# NFC_Demo_Board.net
KiCad netlist of a schematic drawn in EAGLE
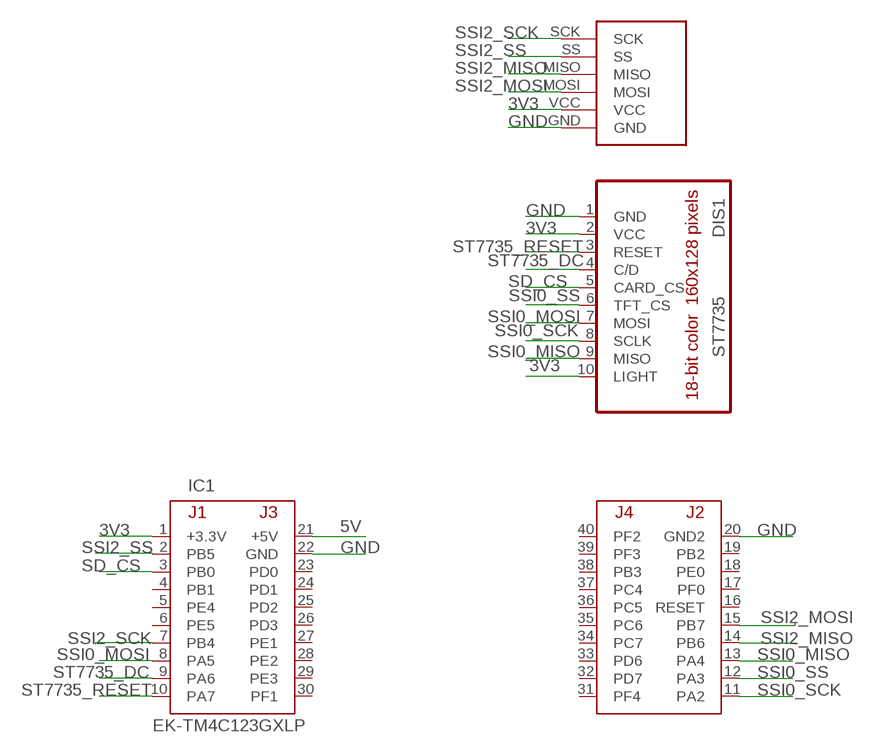
[diagram p0: schematic, sheet 1]

(export (version "E")
  (design (tool "Eeschema 10.0.6"))
  (components
    (comp (ref "DIS1")
      (value "ST7735")
      (footprint "eagle-import:ST7735")
      (libsource (lib "eagle-import") (part "ST7735"))
    )
    (comp (ref "IC1")
      (value "EK-TM4C123GXLP")
      (footprint "eagle-import:TM4C123LAUNCHPAD")
      (libsource (lib "eagle-import") (part "EK-TM4C123GXLP"))
    )
    (comp (ref "U$1")
      (value "ELECHOUSE_PN532_SPI")
      (footprint "eagle-import:ELECHOUSE_PN532_SPI")
      (libsource (lib "eagle-import") (part "ELECHOUSE_PN532_SPI"))
    )
  )
  (nets
    (net (code "1") (name "/3V3") (class "Default")
      (node (ref "DIS1") (pin "10") (pinfunction "LIGHT_10") (pintype "passive"))
      (node (ref "DIS1") (pin "2") (pinfunction "VCC_2") (pintype "power_in"))
      (node (ref "IC1") (pin "1") (pinfunction "+3.3V_1") (pintype "power_in"))
      (node (ref "U$1") (pin "VCC") (pinfunction "VCC_VCC") (pintype "bidirectional"))
    )
    (net (code "2") (name "/5V") (class "Default")
      (node (ref "IC1") (pin "21") (pinfunction "+5V_21") (pintype "power_in"))
    )
    (net (code "3") (name "/GND") (class "Default")
      (node (ref "DIS1") (pin "1") (pinfunction "GND_1") (pintype "power_in"))
      (node (ref "IC1") (pin "20") (pinfunction "GND2_20") (pintype "power_in"))
      (node (ref "IC1") (pin "22") (pinfunction "GND_22") (pintype "power_in"))
      (node (ref "U$1") (pin "GND") (pinfunction "GND_GND") (pintype "bidirectional"))
    )
    (net (code "4") (name "/SD_CS") (class "Default")
      (node (ref "DIS1") (pin "5") (pinfunction "CARD_CS_5") (pintype "input"))
      (node (ref "IC1") (pin "3") (pinfunction "PB0_3") (pintype "bidirectional"))
    )
    (net (code "5") (name "/SSI0_MISO") (class "Default")
      (node (ref "DIS1") (pin "9") (pinfunction "MISO_9") (pintype "output"))
      (node (ref "IC1") (pin "13") (pinfunction "PA4_13") (pintype "bidirectional"))
    )
    (net (code "6") (name "/SSI0_MOSI") (class "Default")
      (node (ref "DIS1") (pin "7") (pinfunction "MOSI_7") (pintype "input"))
      (node (ref "IC1") (pin "8") (pinfunction "PA5_8") (pintype "bidirectional"))
    )
    (net (code "7") (name "/SSI0_SCK") (class "Default")
      (node (ref "DIS1") (pin "8") (pinfunction "SCLK_8") (pintype "input"))
      (node (ref "IC1") (pin "11") (pinfunction "PA2_11") (pintype "bidirectional"))
    )
    (net (code "8") (name "/SSI0_SS") (class "Default")
      (node (ref "DIS1") (pin "6") (pinfunction "TFT_CS_6") (pintype "input"))
      (node (ref "IC1") (pin "12") (pinfunction "PA3_12") (pintype "bidirectional"))
    )
    (net (code "9") (name "/SSI2_MISO") (class "Default")
      (node (ref "IC1") (pin "14") (pinfunction "PB6_14") (pintype "bidirectional"))
      (node (ref "U$1") (pin "MISO") (pinfunction "MISO_MISO") (pintype "bidirectional"))
    )
    (net (code "10") (name "/SSI2_MOSI") (class "Default")
      (node (ref "IC1") (pin "15") (pinfunction "PB7_15") (pintype "bidirectional"))
      (node (ref "U$1") (pin "MOSI") (pinfunction "MOSI_MOSI") (pintype "bidirectional"))
    )
    (net (code "11") (name "/SSI2_SCK") (class "Default")
      (node (ref "IC1") (pin "7") (pinfunction "PB4_7") (pintype "bidirectional"))
      (node (ref "U$1") (pin "SCK") (pinfunction "SCK_SCK") (pintype "bidirectional"))
    )
    (net (code "12") (name "/SSI2_SS") (class "Default")
      (node (ref "IC1") (pin "2") (pinfunction "PB5_2") (pintype "bidirectional"))
      (node (ref "U$1") (pin "SS") (pinfunction "SS_SS") (pintype "bidirectional"))
    )
    (net (code "13") (name "/ST7735_DC") (class "Default")
      (node (ref "DIS1") (pin "4") (pinfunction "C/D_4") (pintype "input"))
      (node (ref "IC1") (pin "9") (pinfunction "PA6_9") (pintype "bidirectional"))
    )
    (net (code "14") (name "/ST7735_RESET") (class "Default")
      (node (ref "DIS1") (pin "3") (pinfunction "RESET_3") (pintype "input"))
      (node (ref "IC1") (pin "10") (pinfunction "PA7_10") (pintype "bidirectional"))
    )
    (net (code "15") (name "unconnected-(IC1-PB1-Pad4)") (class "Default")
      (node (ref "IC1") (pin "4") (pinfunction "PB1_4") (pintype "bidirectional"))
    )
    (net (code "16") (name "unconnected-(IC1-PB2-Pad19)") (class "Default")
      (node (ref "IC1") (pin "19") (pinfunction "PB2_19") (pintype "bidirectional"))
    )
    (net (code "17") (name "unconnected-(IC1-PB3-Pad38)") (class "Default")
      (node (ref "IC1") (pin "38") (pinfunction "PB3_38") (pintype "bidirectional"))
    )
    (net (code "18") (name "unconnected-(IC1-PC4-Pad37)") (class "Default")
      (node (ref "IC1") (pin "37") (pinfunction "PC4_37") (pintype "bidirectional"))
    )
    (net (code "19") (name "unconnected-(IC1-PC5-Pad36)") (class "Default")
      (node (ref "IC1") (pin "36") (pinfunction "PC5_36") (pintype "bidirectional"))
    )
    (net (code "20") (name "unconnected-(IC1-PC6-Pad35)") (class "Default")
      (node (ref "IC1") (pin "35") (pinfunction "PC6_35") (pintype "bidirectional"))
    )
    (net (code "21") (name "unconnected-(IC1-PC7-Pad34)") (class "Default")
      (node (ref "IC1") (pin "34") (pinfunction "PC7_34") (pintype "bidirectional"))
    )
    (net (code "22") (name "unconnected-(IC1-PD0-Pad23)") (class "Default")
      (node (ref "IC1") (pin "23") (pinfunction "PD0_23") (pintype "bidirectional"))
    )
    (net (code "23") (name "unconnected-(IC1-PD1-Pad24)") (class "Default")
      (node (ref "IC1") (pin "24") (pinfunction "PD1_24") (pintype "bidirectional"))
    )
    (net (code "24") (name "unconnected-(IC1-PD2-Pad25)") (class "Default")
      (node (ref "IC1") (pin "25") (pinfunction "PD2_25") (pintype "bidirectional"))
    )
    (net (code "25") (name "unconnected-(IC1-PD3-Pad26)") (class "Default")
      (node (ref "IC1") (pin "26") (pinfunction "PD3_26") (pintype "bidirectional"))
    )
    (net (code "26") (name "unconnected-(IC1-PD6-Pad33)") (class "Default")
      (node (ref "IC1") (pin "33") (pinfunction "PD6_33") (pintype "bidirectional"))
    )
    (net (code "27") (name "unconnected-(IC1-PD7-Pad32)") (class "Default")
      (node (ref "IC1") (pin "32") (pinfunction "PD7_32") (pintype "bidirectional"))
    )
    (net (code "28") (name "unconnected-(IC1-PE0-Pad18)") (class "Default")
      (node (ref "IC1") (pin "18") (pinfunction "PE0_18") (pintype "bidirectional"))
    )
    (net (code "29") (name "unconnected-(IC1-PE1-Pad27)") (class "Default")
      (node (ref "IC1") (pin "27") (pinfunction "PE1_27") (pintype "bidirectional"))
    )
    (net (code "30") (name "unconnected-(IC1-PE2-Pad28)") (class "Default")
      (node (ref "IC1") (pin "28") (pinfunction "PE2_28") (pintype "bidirectional"))
    )
    (net (code "31") (name "unconnected-(IC1-PE3-Pad29)") (class "Default")
      (node (ref "IC1") (pin "29") (pinfunction "PE3_29") (pintype "bidirectional"))
    )
    (net (code "32") (name "unconnected-(IC1-PE4-Pad5)") (class "Default")
      (node (ref "IC1") (pin "5") (pinfunction "PE4_5") (pintype "bidirectional"))
    )
    (net (code "33") (name "unconnected-(IC1-PE5-Pad6)") (class "Default")
      (node (ref "IC1") (pin "6") (pinfunction "PE5_6") (pintype "bidirectional"))
    )
    (net (code "34") (name "unconnected-(IC1-PF0-Pad17)") (class "Default")
      (node (ref "IC1") (pin "17") (pinfunction "PF0_17") (pintype "bidirectional"))
    )
    (net (code "35") (name "unconnected-(IC1-PF1-Pad30)") (class "Default")
      (node (ref "IC1") (pin "30") (pinfunction "PF1_30") (pintype "bidirectional"))
    )
    (net (code "36") (name "unconnected-(IC1-PF2-Pad40)") (class "Default")
      (node (ref "IC1") (pin "40") (pinfunction "PF2_40") (pintype "bidirectional"))
    )
    (net (code "37") (name "unconnected-(IC1-PF3-Pad39)") (class "Default")
      (node (ref "IC1") (pin "39") (pinfunction "PF3_39") (pintype "bidirectional"))
    )
    (net (code "38") (name "unconnected-(IC1-PF4-Pad31)") (class "Default")
      (node (ref "IC1") (pin "31") (pinfunction "PF4_31") (pintype "bidirectional"))
    )
    (net (code "39") (name "unconnected-(IC1-RESET-Pad16)") (class "Default")
      (node (ref "IC1") (pin "16") (pinfunction "RESET_16") (pintype "input"))
    )
  )
)
